# CH32L103C8T6-R0.net
KiCad netlist of a schematic drawn in Altium Designer
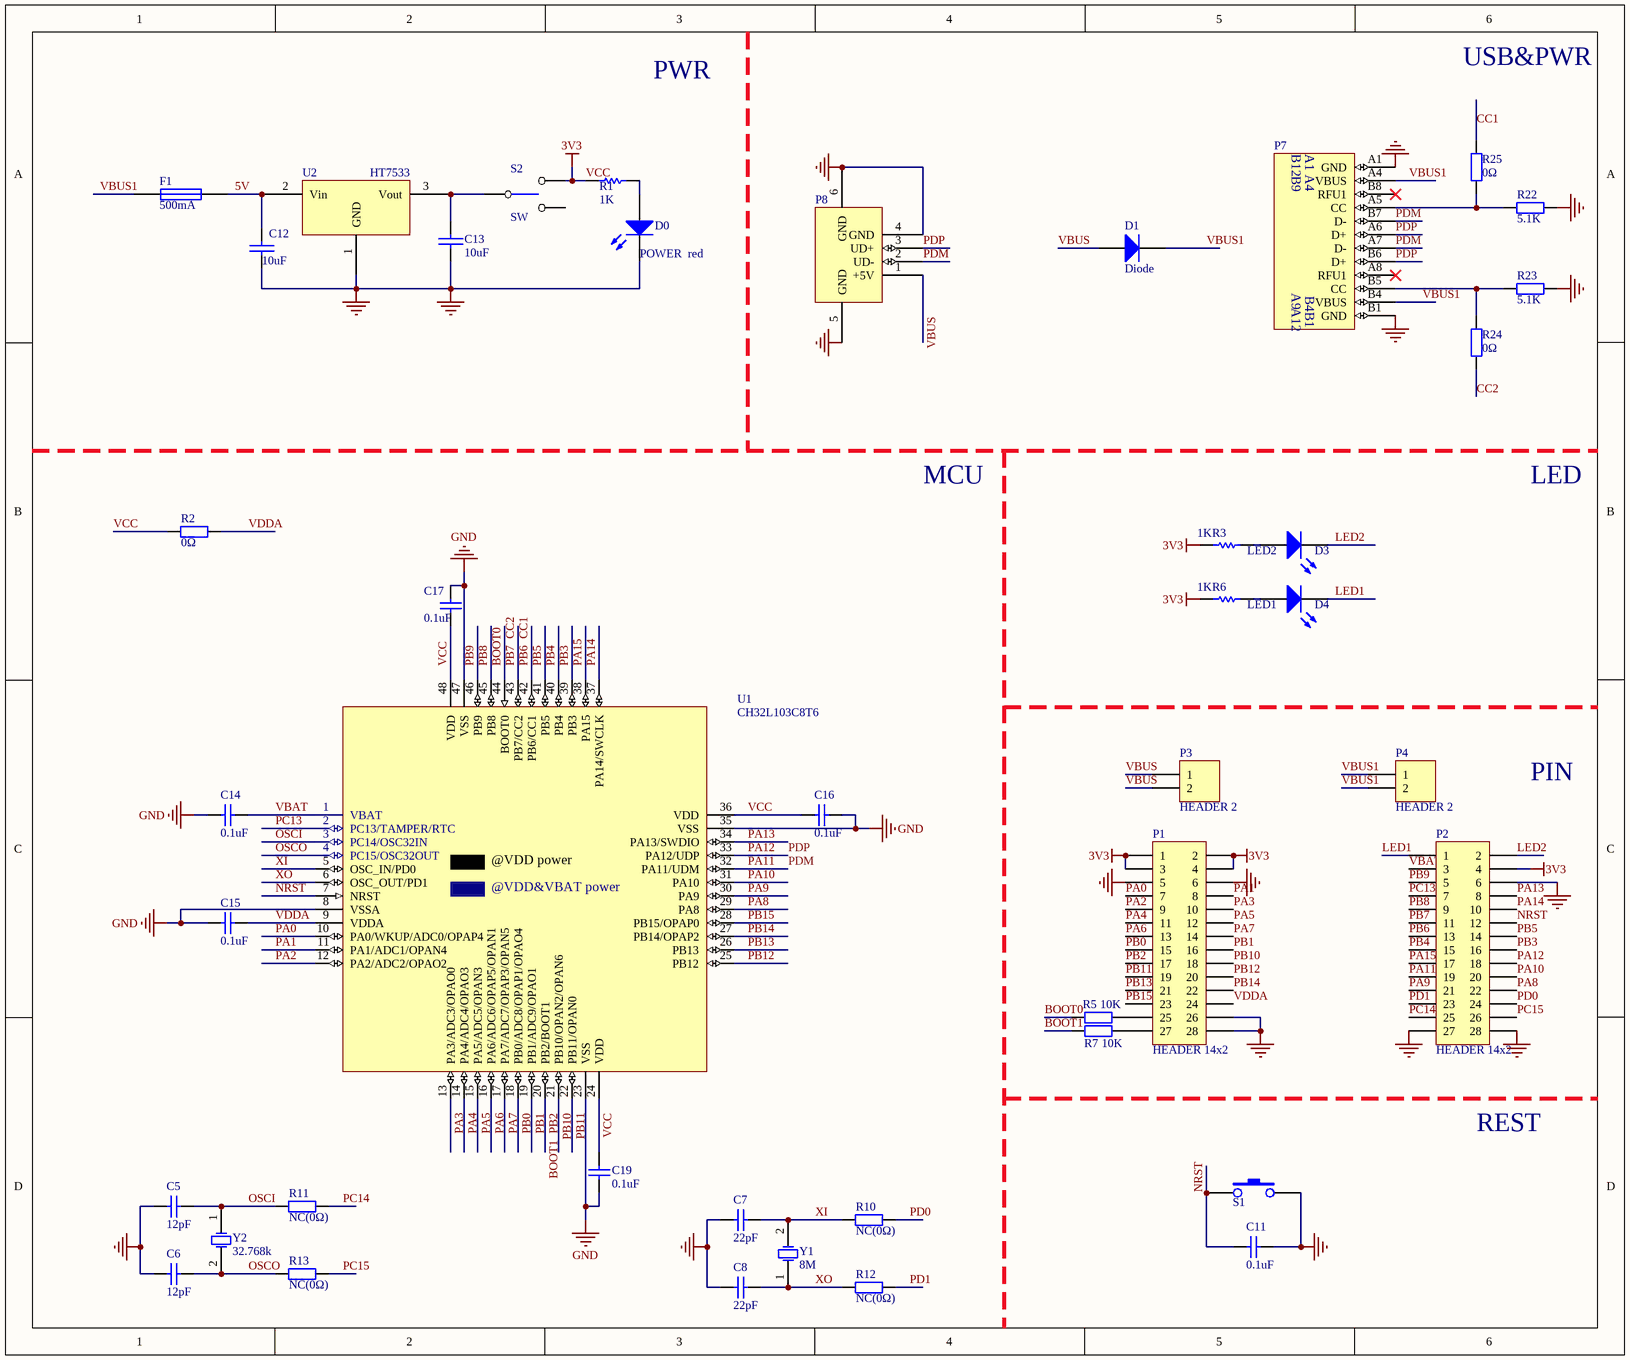
[diagram p0: CH32L103C8T6-R0.SchDoc]

(export (version "E")
  (design (tool "Eeschema 10.0.6"))
  (components
    (comp (ref "C5")
      (value "12pF")
      (footprint "0603_C")
      (description "Capacitor")
      (fields (field (name "PUBLISHER") "Altium Limited"))
      (libsource (lib "*") (part "Cap"))
    )
    (comp (ref "C6")
      (value "12pF")
      (footprint "0603_C")
      (description "Capacitor")
      (fields (field (name "PUBLISHER") "Altium Limited"))
      (libsource (lib "*") (part "Cap"))
    )
    (comp (ref "C7")
      (value "22pF")
      (footprint "0603_C")
      (description "Capacitor")
      (fields (field (name "PUBLISHER") "Altium Limited"))
      (libsource (lib "*") (part "Cap"))
    )
    (comp (ref "C8")
      (value "22pF")
      (footprint "0603_C")
      (description "Capacitor")
      (fields (field (name "PUBLISHER") "Altium Limited"))
      (libsource (lib "*") (part "Cap"))
    )
    (comp (ref "C11")
      (value "0.1uF")
      (footprint "0603_C")
      (description "Capacitor")
      (fields (field (name "PUBLISHER") "Altium Limited"))
      (libsource (lib "*") (part "Cap"))
    )
    (comp (ref "C12")
      (value "10uF")
      (footprint "0603_C")
      (description "Capacitor")
      (libsource (lib "*") (part "CAP"))
    )
    (comp (ref "C13")
      (value "10uF")
      (footprint "0603_C")
      (description "Capacitor")
      (libsource (lib "*") (part "CAP"))
    )
    (comp (ref "C14")
      (value "0.1uF")
      (footprint "0603_C")
      (description "Capacitor")
      (fields (field (name "PUBLISHER") "Altium Limited"))
      (libsource (lib "*") (part "Cap"))
    )
    (comp (ref "C15")
      (value "0.1uF")
      (footprint "0603_C")
      (description "Capacitor")
      (fields (field (name "PUBLISHER") "Altium Limited"))
      (libsource (lib "*") (part "Cap"))
    )
    (comp (ref "C16")
      (value "0.1uF")
      (footprint "0603_C")
      (description "Capacitor")
      (fields (field (name "PUBLISHER") "Altium Limited"))
      (libsource (lib "*") (part "Cap"))
    )
    (comp (ref "C17")
      (value "0.1uF")
      (footprint "0603_C")
      (description "Capacitor")
      (fields (field (name "PUBLISHER") "Altium Limited"))
      (libsource (lib "*") (part "Cap"))
    )
    (comp (ref "C19")
      (value "0.1uF")
      (footprint "0603_C")
      (description "Capacitor")
      (fields (field (name "PUBLISHER") "Altium Limited"))
      (libsource (lib "*") (part "Cap"))
    )
    (comp (ref "D0")
      (value "POWER  red")
      (footprint "0603+")
      (description "Typical INFRARED GaAs LED")
      (fields (field (name "PUBLISHER") "Altium Limited"))
      (libsource (lib "*") (part "LED0"))
    )
    (comp (ref "D1")
      (value "Diode")
      (footprint "SOD-123")
      (description "Default Diode")
      (fields (field (name "PUBLISHER") "Altium Limited"))
      (libsource (lib "Miscellaneous Devices") (part "Diode"))
    )
    (comp (ref "D3")
      (value "LED2")
      (footprint "0603+")
      (description "Typical INFRARED GaAs LED")
      (fields (field (name "PUBLISHER") "Altium Limited"))
      (libsource (lib "*") (part "LED0"))
    )
    (comp (ref "D4")
      (value "LED1")
      (footprint "0603+")
      (description "Typical INFRARED GaAs LED")
      (fields (field (name "PUBLISHER") "Altium Limited"))
      (libsource (lib "*") (part "LED0"))
    )
    (comp (ref "F1")
      (value "500mA")
      (footprint "0603")
      (description "Fuse")
      (libsource (lib "*") (part "FUSE1"))
    )
    (comp (ref "P1")
      (value "HEADER 14x2")
      (footprint "MYPCB:IDC28-2.54MM")
      (description "Header, 14-Pin, Dual row")
      (libsource (lib "wch_sch_others") (part "HEADER 14x2"))
    )
    (comp (ref "P2")
      (value "HEADER 14x2")
      (footprint "MYPCB:IDC28-2.54MM")
      (description "Header, 14-Pin, Dual row")
      (libsource (lib "wch_sch_others") (part "HEADER 14x2"))
    )
    (comp (ref "P3")
      (value "HEADER 2")
      (footprint "SIP2-2.54mm")
      (description "Header, 2-Pin")
      (libsource (lib "wch_sch_others") (part "HEADER 2"))
    )
    (comp (ref "P4")
      (value "HEADER 2")
      (footprint "SIP2-2.54mm")
      (description "Header, 2-Pin")
      (libsource (lib "wch_sch_others") (part "HEADER 2"))
    )
    (comp (ref "P7")
      (value "TYPE-C")
      (footprint "TYPE-C-Receptacle-2.0")
      (libsource (lib "*") (part "TYPE-C1"))
    )
    (comp (ref "P8")
      (value "USB_A")
      (footprint "USBAF")
      (description "USB Port")
      (libsource (lib "*") (part "USB"))
    )
    (comp (ref "R1")
      (value "1K")
      (footprint "0603")
      (description "Semiconductor Resistor")
      (libsource (lib "*") (part "Res Semi"))
    )
    (comp (ref "R2")
      (value "0Ω")
      (footprint "0603")
      (description "Resistor")
      (libsource (lib "Miscellaneous Devices") (part "Res2"))
    )
    (comp (ref "R3")
      (value "1K")
      (footprint "0603")
      (description "Semiconductor Resistor")
      (libsource (lib "*") (part "Res Semi"))
    )
    (comp (ref "R5")
      (value "10K")
      (footprint "0603")
      (description "Resistor")
      (fields (field (name "PUBLISHER") "Altium Limited"))
      (libsource (lib "*") (part "Res2"))
    )
    (comp (ref "R6")
      (value "1K")
      (footprint "0603")
      (description "Semiconductor Resistor")
      (libsource (lib "*") (part "Res Semi"))
    )
    (comp (ref "R7")
      (value "10K")
      (footprint "0603")
      (description "Resistor")
      (fields (field (name "PUBLISHER") "Altium Limited"))
      (libsource (lib "*") (part "Res2"))
    )
    (comp (ref "R10")
      (value "NC(0Ω)")
      (footprint "0603")
      (description "Resistor")
      (libsource (lib "") (part "Res2_1"))
    )
    (comp (ref "R11")
      (value "NC(0Ω)")
      (footprint "0603")
      (description "Resistor")
      (libsource (lib "") (part "Res2_1"))
    )
    (comp (ref "R12")
      (value "NC(0Ω)")
      (footprint "0603")
      (description "Resistor")
      (libsource (lib "") (part "Res2_1"))
    )
    (comp (ref "R13")
      (value "NC(0Ω)")
      (footprint "0603")
      (description "Resistor")
      (libsource (lib "") (part "Res2_1"))
    )
    (comp (ref "R22")
      (value "5.1K")
      (footprint "0603")
      (description "Resistor")
      (libsource (lib "Miscellaneous Devices") (part "Res2"))
    )
    (comp (ref "R23")
      (value "5.1K")
      (footprint "0603")
      (description "Resistor")
      (libsource (lib "Miscellaneous Devices") (part "Res2"))
    )
    (comp (ref "R24")
      (value "0Ω")
      (footprint "0603")
      (description "Resistor")
      (libsource (lib "") (part "Res2_2"))
    )
    (comp (ref "R25")
      (value "0Ω")
      (footprint "0603")
      (description "Resistor")
      (libsource (lib "") (part "Res2_2"))
    )
    (comp (ref "S1") (value "KEY") (footprint "贴片按键") (libsource (lib "*") (part "KEY")))
    (comp (ref "S2") (value "SW") (footprint "SW1") (libsource (lib "*") (part "SW")))
    (comp (ref "U1")
      (value "CH32L103C8T6")
      (footprint "LQFP48")
      (description "RISC-V LMD-MCU, 96MHz, USB, Type-C/PD, CAN, OPA, lower power")
      (libsource (lib "CHXXX") (part "CH32L103C8T6"))
    )
    (comp (ref "U2")
      (value "HT7533")
      (footprint "SOT-89")
      (libsource (lib "wch_sch_others") (part "1117-3.3V"))
    )
    (comp (ref "Y1")
      (value "8M")
      (footprint "XT_AT49")
      (description "Crystal Oscillator")
      (fields (field (name "PUBLISHER") "Altium Limited"))
      (libsource (lib "*") (part "XTAL"))
    )
    (comp (ref "Y2")
      (value "32.768k")
      (footprint "FC-135")
      (description "Crystal Oscillator")
      (fields (field (name "PUBLISHER") "Altium Limited"))
      (libsource (lib "*") (part "XTAL"))
    )
  )
  (nets
    (net (code "1") (name "/5V") (class "Default")
      (node (ref "C12") (pin "1") (pinfunction "1_1") (pintype "passive"))
      (node (ref "F1") (pin "2") (pinfunction "2_2") (pintype "passive"))
      (node (ref "U2") (pin "2") (pinfunction "Vin_2") (pintype "passive"))
    )
    (net (code "3") (name "/BOOT0") (class "Default")
      (node (ref "R5") (pin "1") (pinfunction "1_1") (pintype "passive"))
      (node (ref "U1") (pin "44") (pinfunction "BOOT0_44") (pintype "input"))
    )
    (net (code "4") (name "/BOOT1") (class "Default")
      (node (ref "P1") (pin "17") (pinfunction "17_17") (pintype "passive"))
      (node (ref "R7") (pin "1") (pinfunction "1_1") (pintype "passive"))
      (node (ref "U1") (pin "20") (pinfunction "PB2/BOOT1_20") (pintype "bidirectional"))
    )
    (net (code "5") (name "/CC1") (class "Default")
      (node (ref "P2") (pin "13") (pinfunction "13_13") (pintype "passive"))
      (node (ref "R25") (pin "2") (pinfunction "2_2") (pintype "passive"))
      (node (ref "U1") (pin "42") (pinfunction "PB6/CC1_42") (pintype "bidirectional"))
    )
    (net (code "6") (name "/CC2") (class "Default")
      (node (ref "P2") (pin "11") (pinfunction "11_11") (pintype "passive"))
      (node (ref "R24") (pin "1") (pinfunction "1_1") (pintype "passive"))
      (node (ref "U1") (pin "43") (pinfunction "PB7/CC2_43") (pintype "bidirectional"))
    )
    (net (code "7") (name "/LED1") (class "Default")
      (node (ref "D4") (pin "2") (pinfunction "K_2") (pintype "passive"))
      (node (ref "P2") (pin "1") (pinfunction "1_1") (pintype "passive"))
    )
    (net (code "8") (name "/LED2") (class "Default")
      (node (ref "D3") (pin "2") (pinfunction "K_2") (pintype "passive"))
      (node (ref "P2") (pin "2") (pinfunction "2_2") (pintype "passive"))
    )
    (net (code "9") (name "/NRST") (class "Default")
      (node (ref "C11") (pin "2") (pinfunction "2_2") (pintype "passive"))
      (node (ref "P2") (pin "12") (pinfunction "12_12") (pintype "passive"))
      (node (ref "S1") (pin "1") (pinfunction "1_1") (pintype "passive"))
      (node (ref "U1") (pin "7") (pinfunction "NRST_7") (pintype "input"))
    )
    (net (code "10") (name "/OSCI") (class "Default")
      (node (ref "C5") (pin "1") (pinfunction "1_1") (pintype "passive"))
      (node (ref "R11") (pin "2") (pinfunction "2_2") (pintype "passive"))
      (node (ref "U1") (pin "3") (pinfunction "PC14/OSC32IN_3") (pintype "bidirectional"))
      (node (ref "Y2") (pin "1") (pinfunction "OSC1_1") (pintype "passive"))
    )
    (net (code "11") (name "/OSCO") (class "Default")
      (node (ref "C6") (pin "1") (pinfunction "1_1") (pintype "passive"))
      (node (ref "R13") (pin "2") (pinfunction "2_2") (pintype "passive"))
      (node (ref "U1") (pin "4") (pinfunction "PC15/OSC32OUT_4") (pintype "bidirectional"))
      (node (ref "Y2") (pin "2") (pinfunction "OSC2_2") (pintype "passive"))
    )
    (net (code "12") (name "/PA0") (class "Default")
      (node (ref "P1") (pin "7") (pinfunction "7_7") (pintype "passive"))
      (node (ref "U1") (pin "10") (pinfunction "PA0/WKUP/ADC0/OPAP4_10") (pintype "bidirectional"))
    )
    (net (code "13") (name "/PA1") (class "Default")
      (node (ref "P1") (pin "8") (pinfunction "8_8") (pintype "passive"))
      (node (ref "U1") (pin "11") (pinfunction "PA1/ADC1/OPAN4_11") (pintype "bidirectional"))
    )
    (net (code "14") (name "/PA2") (class "Default")
      (node (ref "P1") (pin "9") (pinfunction "9_9") (pintype "passive"))
      (node (ref "U1") (pin "12") (pinfunction "PA2/ADC2/OPAO2_12") (pintype "bidirectional"))
    )
    (net (code "15") (name "/PA3") (class "Default")
      (node (ref "P1") (pin "10") (pinfunction "10_10") (pintype "passive"))
      (node (ref "U1") (pin "13") (pinfunction "PA3/ADC3/OPAO0_13") (pintype "bidirectional"))
    )
    (net (code "16") (name "/PA4") (class "Default")
      (node (ref "P1") (pin "11") (pinfunction "11_11") (pintype "passive"))
      (node (ref "U1") (pin "14") (pinfunction "PA4/ADC4/OPAO3_14") (pintype "bidirectional"))
    )
    (net (code "17") (name "/PA5") (class "Default")
      (node (ref "P1") (pin "12") (pinfunction "12_12") (pintype "passive"))
      (node (ref "U1") (pin "15") (pinfunction "PA5/ADC5/OPAN3_15") (pintype "bidirectional"))
    )
    (net (code "18") (name "/PA6") (class "Default")
      (node (ref "P1") (pin "13") (pinfunction "13_13") (pintype "passive"))
      (node (ref "U1") (pin "16") (pinfunction "PA6/ADC6/OPAP5/OPAN1_16") (pintype "bidirectional"))
    )
    (net (code "19") (name "/PA7") (class "Default")
      (node (ref "P1") (pin "14") (pinfunction "14_14") (pintype "passive"))
      (node (ref "U1") (pin "17") (pinfunction "PA7/ADC7/OPAP3/OPAN5_17") (pintype "bidirectional"))
    )
    (net (code "20") (name "/PA8") (class "Default")
      (node (ref "P2") (pin "22") (pinfunction "22_22") (pintype "passive"))
      (node (ref "U1") (pin "29") (pinfunction "PA8_29") (pintype "bidirectional"))
    )
    (net (code "21") (name "/PA9") (class "Default")
      (node (ref "P2") (pin "21") (pinfunction "21_21") (pintype "passive"))
      (node (ref "U1") (pin "30") (pinfunction "PA9_30") (pintype "bidirectional"))
    )
    (net (code "22") (name "/PA10") (class "Default")
      (node (ref "P2") (pin "20") (pinfunction "20_20") (pintype "passive"))
      (node (ref "U1") (pin "31") (pinfunction "PA10_31") (pintype "bidirectional"))
    )
    (net (code "23") (name "/PA11") (class "Default")
      (node (ref "P2") (pin "19") (pinfunction "19_19") (pintype "passive"))
      (node (ref "P7") (pin "A7") (pinfunction "D-_A7") (pintype "bidirectional"))
      (node (ref "P7") (pin "B7") (pinfunction "D-_B7") (pintype "bidirectional"))
      (node (ref "P8") (pin "2") (pinfunction "UD-_2") (pintype "bidirectional"))
      (node (ref "U1") (pin "32") (pinfunction "PA11/UDM_32") (pintype "bidirectional"))
    )
    (net (code "24") (name "/PA12") (class "Default")
      (node (ref "P2") (pin "18") (pinfunction "18_18") (pintype "passive"))
      (node (ref "P7") (pin "A6") (pinfunction "D+_A6") (pintype "bidirectional"))
      (node (ref "P7") (pin "B6") (pinfunction "D+_B6") (pintype "bidirectional"))
      (node (ref "P8") (pin "3") (pinfunction "UD+_3") (pintype "bidirectional"))
      (node (ref "U1") (pin "33") (pinfunction "PA12/UDP_33") (pintype "bidirectional"))
    )
    (net (code "25") (name "/PA13") (class "Default")
      (node (ref "P2") (pin "8") (pinfunction "8_8") (pintype "passive"))
      (node (ref "U1") (pin "34") (pinfunction "PA13/SWDIO_34") (pintype "bidirectional"))
    )
    (net (code "26") (name "/PA14") (class "Default")
      (node (ref "P2") (pin "10") (pinfunction "10_10") (pintype "passive"))
      (node (ref "U1") (pin "37") (pinfunction "PA14/SWCLK_37") (pintype "bidirectional"))
    )
    (net (code "27") (name "/PA15") (class "Default")
      (node (ref "P2") (pin "17") (pinfunction "17_17") (pintype "passive"))
      (node (ref "U1") (pin "38") (pinfunction "PA15_38") (pintype "bidirectional"))
    )
    (net (code "28") (name "/PB0") (class "Default")
      (node (ref "P1") (pin "15") (pinfunction "15_15") (pintype "passive"))
      (node (ref "U1") (pin "18") (pinfunction "PB0/ADC8/OPAP1/OPAO4_18") (pintype "bidirectional"))
    )
    (net (code "29") (name "/PB1") (class "Default")
      (node (ref "P1") (pin "16") (pinfunction "16_16") (pintype "passive"))
      (node (ref "U1") (pin "19") (pinfunction "PB1/ADC9/OPAO1_19") (pintype "bidirectional"))
    )
    (net (code "30") (name "/PB3") (class "Default")
      (node (ref "P2") (pin "16") (pinfunction "16_16") (pintype "passive"))
      (node (ref "U1") (pin "39") (pinfunction "PB3_39") (pintype "bidirectional"))
    )
    (net (code "31") (name "/PB4") (class "Default")
      (node (ref "P2") (pin "15") (pinfunction "15_15") (pintype "passive"))
      (node (ref "U1") (pin "40") (pinfunction "PB4_40") (pintype "bidirectional"))
    )
    (net (code "32") (name "/PB5") (class "Default")
      (node (ref "P2") (pin "14") (pinfunction "14_14") (pintype "passive"))
      (node (ref "U1") (pin "41") (pinfunction "PB5_41") (pintype "bidirectional"))
    )
    (net (code "33") (name "/PB8") (class "Default")
      (node (ref "P2") (pin "9") (pinfunction "9_9") (pintype "passive"))
      (node (ref "U1") (pin "45") (pinfunction "PB8_45") (pintype "bidirectional"))
    )
    (net (code "34") (name "/PB9") (class "Default")
      (node (ref "P2") (pin "5") (pinfunction "5_5") (pintype "passive"))
      (node (ref "U1") (pin "46") (pinfunction "PB9_46") (pintype "bidirectional"))
    )
    (net (code "35") (name "/PB10") (class "Default")
      (node (ref "P1") (pin "18") (pinfunction "18_18") (pintype "passive"))
      (node (ref "U1") (pin "21") (pinfunction "PB10/OPAN2/OPAN6_21") (pintype "bidirectional"))
    )
    (net (code "36") (name "/PB11") (class "Default")
      (node (ref "P1") (pin "19") (pinfunction "19_19") (pintype "passive"))
      (node (ref "U1") (pin "22") (pinfunction "PB11/OPAN0_22") (pintype "bidirectional"))
    )
    (net (code "37") (name "/PB12") (class "Default")
      (node (ref "P1") (pin "20") (pinfunction "20_20") (pintype "passive"))
      (node (ref "U1") (pin "25") (pinfunction "PB12_25") (pintype "bidirectional"))
    )
    (net (code "38") (name "/PB13") (class "Default")
      (node (ref "P1") (pin "21") (pinfunction "21_21") (pintype "passive"))
      (node (ref "U1") (pin "26") (pinfunction "PB13_26") (pintype "bidirectional"))
    )
    (net (code "39") (name "/PB14") (class "Default")
      (node (ref "P1") (pin "22") (pinfunction "22_22") (pintype "passive"))
      (node (ref "U1") (pin "27") (pinfunction "PB14/OPAP2_27") (pintype "bidirectional"))
    )
    (net (code "40") (name "/PB15") (class "Default")
      (node (ref "P1") (pin "23") (pinfunction "23_23") (pintype "passive"))
      (node (ref "U1") (pin "28") (pinfunction "PB15/OPAP0_28") (pintype "bidirectional"))
    )
    (net (code "41") (name "/PC13") (class "Default")
      (node (ref "P2") (pin "7") (pinfunction "7_7") (pintype "passive"))
      (node (ref "U1") (pin "2") (pinfunction "PC13/TAMPER/RTC_2") (pintype "bidirectional"))
    )
    (net (code "42") (name "/PC14") (class "Default")
      (node (ref "P2") (pin "25") (pinfunction "25_25") (pintype "passive"))
      (node (ref "R11") (pin "1") (pinfunction "1_1") (pintype "passive"))
    )
    (net (code "43") (name "/PC15") (class "Default")
      (node (ref "P2") (pin "26") (pinfunction "26_26") (pintype "passive"))
      (node (ref "R13") (pin "1") (pinfunction "1_1") (pintype "passive"))
    )
    (net (code "44") (name "/PD0") (class "Default")
      (node (ref "P2") (pin "24") (pinfunction "24_24") (pintype "passive"))
      (node (ref "R10") (pin "1") (pinfunction "1_1") (pintype "passive"))
    )
    (net (code "45") (name "/PD1") (class "Default")
      (node (ref "P2") (pin "23") (pinfunction "23_23") (pintype "passive"))
      (node (ref "R12") (pin "1") (pinfunction "1_1") (pintype "passive"))
    )
    (net (code "46") (name "/VBAT") (class "Default")
      (node (ref "C14") (pin "1") (pinfunction "1_1") (pintype "passive"))
      (node (ref "P2") (pin "3") (pinfunction "3_3") (pintype "passive"))
      (node (ref "U1") (pin "1") (pinfunction "VBAT_1") (pintype "power_in"))
    )
    (net (code "47") (name "/VBUS") (class "Default")
      (node (ref "D1") (pin "1") (pinfunction "A_1") (pintype "passive"))
      (node (ref "P3") (pin "1") (pinfunction "1_1") (pintype "passive"))
      (node (ref "P3") (pin "2") (pinfunction "2_2") (pintype "passive"))
      (node (ref "P8") (pin "1") (pinfunction "+5V_1") (pintype "power_in"))
    )
    (net (code "48") (name "/VBUS1") (class "Default")
      (node (ref "D1") (pin "2") (pinfunction "K_2") (pintype "passive"))
      (node (ref "F1") (pin "1") (pinfunction "1_1") (pintype "passive"))
      (node (ref "P4") (pin "1") (pinfunction "1_1") (pintype "passive"))
      (node (ref "P4") (pin "2") (pinfunction "2_2") (pintype "passive"))
      (node (ref "P7") (pin "A4") (pinfunction "VBUS_A4") (pintype "bidirectional"))
      (node (ref "P7") (pin "B4") (pinfunction "VBUS_B4") (pintype "bidirectional"))
    )
    (net (code "49") (name "/VDDA") (class "Default")
      (node (ref "C15") (pin "1") (pinfunction "1_1") (pintype "passive"))
      (node (ref "P1") (pin "24") (pinfunction "24_24") (pintype "passive"))
      (node (ref "R2") (pin "2") (pinfunction "2_2") (pintype "passive"))
      (node (ref "U1") (pin "9") (pinfunction "VDDA_9") (pintype "power_in"))
    )
    (net (code "50") (name "/XI") (class "Default")
      (node (ref "C7") (pin "2") (pinfunction "2_2") (pintype "passive"))
      (node (ref "R10") (pin "2") (pinfunction "2_2") (pintype "passive"))
      (node (ref "U1") (pin "5") (pinfunction "OSC_IN/PD0_5") (pintype "bidirectional"))
      (node (ref "Y1") (pin "2") (pinfunction "OSC2_2") (pintype "passive"))
    )
    (net (code "51") (name "/XO") (class "Default")
      (node (ref "C8") (pin "2") (pinfunction "2_2") (pintype "passive"))
      (node (ref "R12") (pin "2") (pinfunction "2_2") (pintype "passive"))
      (node (ref "U1") (pin "6") (pinfunction "OSC_OUT/PD1_6") (pintype "bidirectional"))
      (node (ref "Y1") (pin "1") (pinfunction "OSC1_1") (pintype "passive"))
    )
    (net (code "52") (name "3V3") (class "Default")
      (node (ref "C16") (pin "1") (pinfunction "1_1") (pintype "passive"))
      (node (ref "C17") (pin "2") (pinfunction "2_2") (pintype "passive"))
      (node (ref "C19") (pin "2") (pinfunction "2_2") (pintype "passive"))
      (node (ref "P1") (pin "1") (pinfunction "1_1") (pintype "passive"))
      (node (ref "P1") (pin "2") (pinfunction "2_2") (pintype "passive"))
      (node (ref "P1") (pin "3") (pinfunction "3_3") (pintype "passive"))
      (node (ref "P1") (pin "4") (pinfunction "4_4") (pintype "passive"))
      (node (ref "P2") (pin "4") (pinfunction "4_4") (pintype "passive"))
      (node (ref "R1") (pin "2") (pinfunction "2_2") (pintype "passive"))
      (node (ref "R2") (pin "1") (pinfunction "1_1") (pintype "passive"))
      (node (ref "R3") (pin "1") (pinfunction "1_1") (pintype "passive"))
      (node (ref "R6") (pin "1") (pinfunction "1_1") (pintype "passive"))
      (node (ref "S2") (pin "3") (pinfunction "3_3") (pintype "passive"))
      (node (ref "U1") (pin "24") (pinfunction "VDD_24") (pintype "power_in"))
      (node (ref "U1") (pin "36") (pinfunction "VDD_36") (pintype "power_in"))
      (node (ref "U1") (pin "48") (pinfunction "VDD_48") (pintype "power_in"))
    )
    (net (code "53") (name "GND") (class "Default")
      (node (ref "C11") (pin "1") (pinfunction "1_1") (pintype "passive"))
      (node (ref "C12") (pin "2") (pinfunction "2_2") (pintype "passive"))
      (node (ref "C13") (pin "2") (pinfunction "2_2") (pintype "passive"))
      (node (ref "C14") (pin "2") (pinfunction "2_2") (pintype "passive"))
      (node (ref "C15") (pin "2") (pinfunction "2_2") (pintype "passive"))
      (node (ref "C16") (pin "2") (pinfunction "2_2") (pintype "passive"))
      (node (ref "C17") (pin "1") (pinfunction "1_1") (pintype "passive"))
      (node (ref "C19") (pin "1") (pinfunction "1_1") (pintype "passive"))
      (node (ref "C5") (pin "2") (pinfunction "2_2") (pintype "passive"))
      (node (ref "C6") (pin "2") (pinfunction "2_2") (pintype "passive"))
      (node (ref "C7") (pin "1") (pinfunction "1_1") (pintype "passive"))
      (node (ref "C8") (pin "1") (pinfunction "1_1") (pintype "passive"))
      (node (ref "D0") (pin "2") (pinfunction "K_2") (pintype "passive"))
      (node (ref "P1") (pin "26") (pinfunction "26_26") (pintype "passive"))
      (node (ref "P1") (pin "28") (pinfunction "28_28") (pintype "passive"))
      (node (ref "P1") (pin "5") (pinfunction "5_5") (pintype "passive"))
      (node (ref "P1") (pin "6") (pinfunction "6_6") (pintype "passive"))
      (node (ref "P2") (pin "27") (pinfunction "27_27") (pintype "passive"))
      (node (ref "P2") (pin "28") (pinfunction "28_28") (pintype "passive"))
      (node (ref "P2") (pin "6") (pinfunction "6_6") (pintype "passive"))
      (node (ref "P7") (pin "A1") (pinfunction "GND_A1") (pintype "bidirectional"))
      (node (ref "P7") (pin "B1") (pinfunction "GND_B1") (pintype "bidirectional"))
      (node (ref "P8") (pin "4") (pinfunction "GND_4") (pintype "power_in"))
      (node (ref "P8") (pin "5") (pinfunction "GND_5") (pintype "power_in"))
      (node (ref "P8") (pin "6") (pinfunction "GND_6") (pintype "power_in"))
      (node (ref "R22") (pin "2") (pinfunction "2_2") (pintype "passive"))
      (node (ref "R23") (pin "2") (pinfunction "2_2") (pintype "passive"))
      (node (ref "S1") (pin "2") (pinfunction "2_2") (pintype "passive"))
      (node (ref "U1") (pin "23") (pinfunction "VSS_23") (pintype "power_in"))
      (node (ref "U1") (pin "35") (pinfunction "VSS_35") (pintype "power_in"))
      (node (ref "U1") (pin "47") (pinfunction "VSS_47") (pintype "power_in"))
      (node (ref "U1") (pin "8") (pinfunction "VSSA_8") (pintype "power_in"))
      (node (ref "U2") (pin "1") (pinfunction "GND_1") (pintype "passive"))
    )
    (net (code "54") (name "Net-(D0-A)") (class "Default")
      (node (ref "D0") (pin "1") (pinfunction "A_1") (pintype "passive"))
      (node (ref "R1") (pin "1") (pinfunction "1_1") (pintype "passive"))
    )
    (net (code "55") (name "Net-(D3-A)") (class "Default")
      (node (ref "D3") (pin "1") (pinfunction "A_1") (pintype "passive"))
      (node (ref "R3") (pin "2") (pinfunction "2_2") (pintype "passive"))
    )
    (net (code "56") (name "Net-(D4-A)") (class "Default")
      (node (ref "D4") (pin "1") (pinfunction "A_1") (pintype "passive"))
      (node (ref "R6") (pin "2") (pinfunction "2_2") (pintype "passive"))
    )
    (net (code "57") (name "Net-(P1-Pad25)") (class "Default")
      (node (ref "P1") (pin "25") (pinfunction "25_25") (pintype "passive"))
      (node (ref "R5") (pin "2") (pinfunction "2_2") (pintype "passive"))
    )
    (net (code "58") (name "Net-(P1-Pad27)") (class "Default")
      (node (ref "P1") (pin "27") (pinfunction "27_27") (pintype "passive"))
      (node (ref "R7") (pin "2") (pinfunction "2_2") (pintype "passive"))
    )
    (net (code "59") (name "Net-(P7-CC-PadA5)") (class "Default")
      (node (ref "P7") (pin "A5") (pinfunction "CC_A5") (pintype "bidirectional"))
      (node (ref "R22") (pin "1") (pinfunction "1_1") (pintype "passive"))
      (node (ref "R25") (pin "1") (pinfunction "1_1") (pintype "passive"))
    )
    (net (code "60") (name "Net-(P7-CC-PadB5)") (class "Default")
      (node (ref "P7") (pin "B5") (pinfunction "CC_B5") (pintype "bidirectional"))
      (node (ref "R23") (pin "1") (pinfunction "1_1") (pintype "passive"))
      (node (ref "R24") (pin "2") (pinfunction "2_2") (pintype "passive"))
    )
    (net (code "61") (name "Net-(U2-Vout)") (class "Default")
      (node (ref "C13") (pin "1") (pinfunction "1_1") (pintype "passive"))
      (node (ref "S2") (pin "1") (pinfunction "1_1") (pintype "passive"))
      (node (ref "U2") (pin "3") (pinfunction "Vout_3") (pintype "passive"))
    )
    (net (code "62") (name "unconnected-(P7-RFU1-PadA8)") (class "Default")
      (node (ref "P7") (pin "A8") (pinfunction "RFU1_A8") (pintype "bidirectional+no_connect"))
    )
    (net (code "63") (name "unconnected-(P7-RFU1-PadB8)") (class "Default")
      (node (ref "P7") (pin "B8") (pinfunction "RFU1_B8") (pintype "bidirectional+no_connect"))
    )
    (net (code "64") (name "unconnected-(S2-Pad2)") (class "Default")
      (node (ref "S2") (pin "2") (pinfunction "2_2") (pintype "passive"))
    )
  )
)
